# Project-PCB.net
KiCad netlist of a schematic drawn in Altium Designer
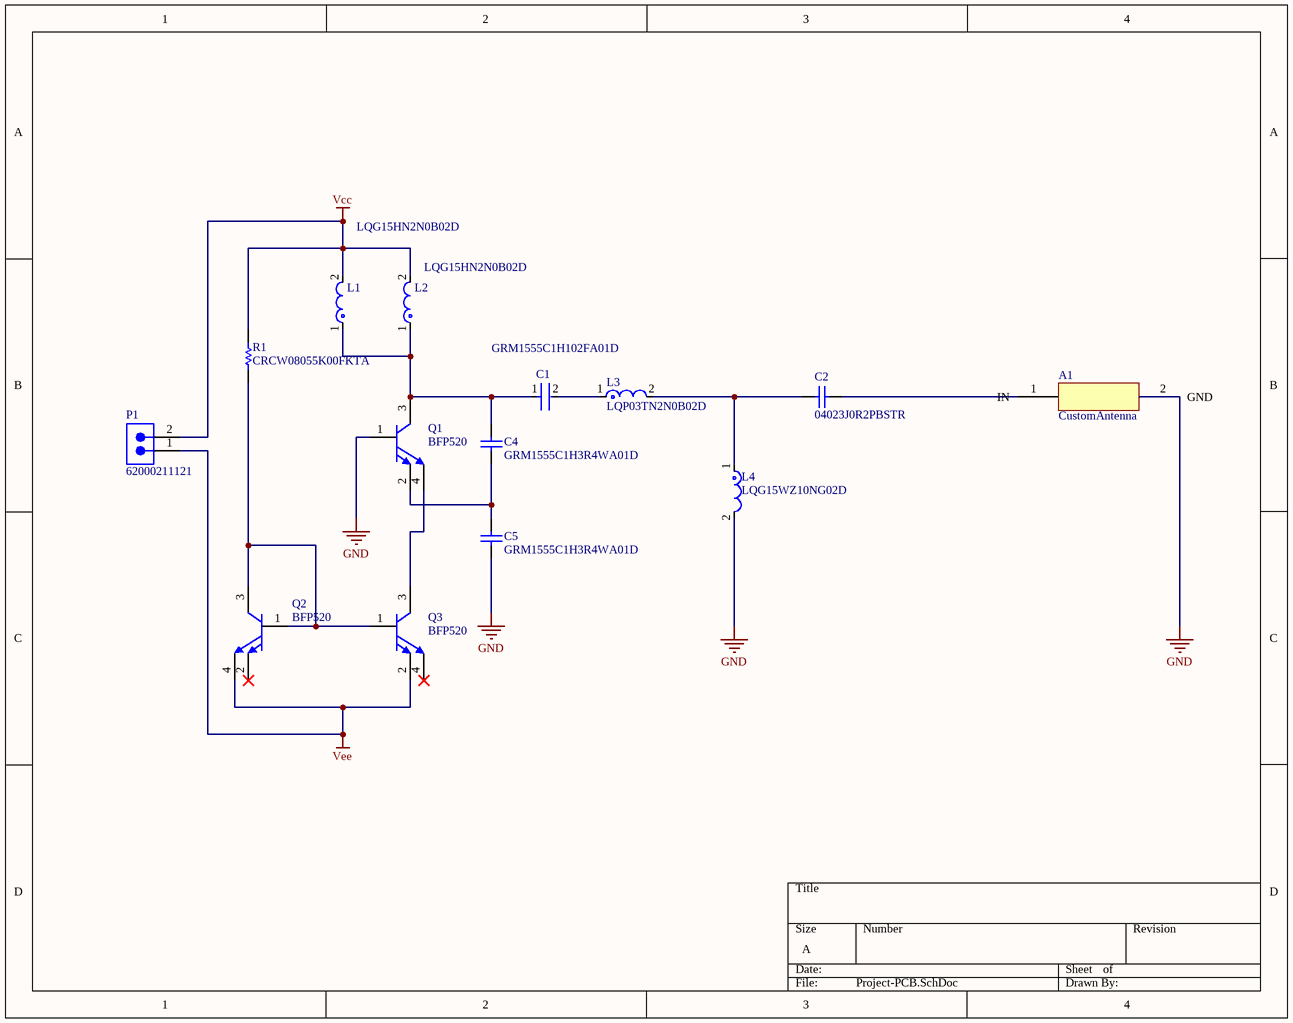
[diagram p0: Project-PCB.SchDoc]

(export (version "E")
  (design (tool "Eeschema 10.0.6"))
  (components
    (comp (ref "A1")
      (value "CustomAntenna")
      (footprint "CustomAntennaFootprint")
      (description "Custom Antenna from CST")
      (libsource (lib "AntennaLib") (part "CustomAntenna"))
    )
    (comp (ref "C1")
      (value "GRM1555C1H102FA01D")
      (footprint "FP-GRM155-0_05-IPC_B")
      (description "Chip Multilayer Ceramic Capacitors for General Purpose, 0402, 1000pF, C0G, 30ppm/°C, 1%, 50V")
      (fields (field (name "TOLERANCE") "1%") (field (name "VOLTAGE") "50V"))
      (libsource (lib "Altium Content Vault") (part "02cd4be3c70576c341d710602a673aa"))
    )
    (comp (ref "C2")
      (value "04023J0R2PBSTR")
      (footprint "CAPC1006X50X20LL10T10")
      (fields (field (name "MANUFACTURER") "AVX Interconnect / Elco"))
      (libsource (lib "Altium Content Vault") (part "CAP"))
    )
    (comp (ref "C4")
      (value "GRM1555C1H3R4WA01D")
      (footprint "CAPC1005X55X25ML05T10")
      (fields (field (name "MANUFACTURER") "Murata"))
      (libsource (lib "Altium Content Vault") (part "CAP"))
    )
    (comp (ref "C5")
      (value "GRM1555C1H3R4WA01D")
      (footprint "CAPC1005X55X25ML05T10")
      (fields (field (name "MANUFACTURER") "Murata"))
      (libsource (lib "Altium Content Vault") (part "CAP"))
    )
    (comp (ref "L1")
      (value "LQG15HN2N0B02D")
      (footprint "FP-LQG15HH_02-MFG")
      (description "Multilayer type RF Inductor 2nH ±0.1nH 0.09Ω 900mA 0402")
      (libsource (lib "Altium Content Vault") (part "4cc4b267dca4c8e51f7102f422741d8"))
    )
    (comp (ref "L2")
      (value "LQG15HN2N0B02D")
      (footprint "FP-LQG15HH_02-MFG")
      (description "Multilayer type RF Inductor 2nH ±0.1nH 0.09Ω 900mA 0402")
      (libsource (lib "Altium Content Vault") (part "4cc4b267dca4c8e51f7102f422741d8"))
    )
    (comp (ref "L3")
      (value "LQP03TN2N0B02D")
      (footprint "FP-LQP03TG_02-IPC_A")
      (description "Film type RF Inductor 2nH ±0.1nH 600mA 0.15Ω 0201 (0603)")
      (libsource (lib "Altium Content Vault") (part "4cc4b267dca4c8e51f7102f422741d8"))
    )
    (comp (ref "L4")
      (value "LQG15WZ10NG02D")
      (footprint "FP-LQG15WH_02-IPC_A")
      (description "Multilayer type Inductor for Automotive 10nH ±2% 0.19Ω 500mA 0402")
      (libsource (lib "Altium Content Vault") (part "4cc4b267dca4c8e51f7102f422741d8"))
    )
    (comp (ref "P1")
      (value "62000211121")
      (footprint "62000211121")
      (libsource (lib "Altium Content Vault") (part "Header_Male_1R_02P"))
    )
    (comp (ref "Q1")
      (value "BFP520")
      (footprint "INF-SOT343_V")
      (description "NPN Silicon RF Transistor, 2.5 V VCEO, 40 mA IC, 23.5 dB Gmax, SOT343, Green")
      (fields (field (name "MANUFACTURER") "Infineon"))
      (libsource (lib "Altium Content Vault") (part "INF-BFP520-4"))
    )
    (comp (ref "Q2")
      (value "BFP520")
      (footprint "INF-SOT343_V")
      (description "NPN Silicon RF Transistor, 2.5 V VCEO, 40 mA IC, 23.5 dB Gmax, SOT343, Green")
      (fields (field (name "MANUFACTURER") "Infineon"))
      (libsource (lib "Altium Content Vault") (part "INF-BFP520-4"))
    )
    (comp (ref "Q3")
      (value "BFP520")
      (footprint "INF-SOT343_V")
      (description "NPN Silicon RF Transistor, 2.5 V VCEO, 40 mA IC, 23.5 dB Gmax, SOT343, Green")
      (fields (field (name "MANUFACTURER") "Infineon"))
      (libsource (lib "Altium Content Vault") (part "INF-BFP520-4"))
    )
    (comp (ref "R1")
      (value "CRCW08055K00FKTA")
      (footprint "RESC2013X50X30ML20T20")
      (fields (field (name "MANUFACTURER") "Vishay Dale"))
      (libsource (lib "Altium Content Vault") (part "RES"))
    )
  )
  (nets
    (net (code "1") (name "GND") (class "Default")
      (node (ref "A1") (pin "2") (pinfunction "GND_2") (pintype "passive"))
      (node (ref "C5") (pin "1") (pinfunction "1_1") (pintype "passive"))
      (node (ref "L4") (pin "2") (pinfunction "2_2") (pintype "passive"))
      (node (ref "Q1") (pin "1") (pinfunction "B_1") (pintype "passive"))
    )
    (net (code "2") (name "Net-(A1-IN)") (class "Default")
      (node (ref "A1") (pin "1") (pinfunction "IN_1") (pintype "passive"))
      (node (ref "C2") (pin "2") (pinfunction "2_2") (pintype "passive"))
    )
    (net (code "3") (name "Net-(C1-Pad2)") (class "Default")
      (node (ref "C1") (pin "2") (pinfunction "2_2") (pintype "passive"))
      (node (ref "L3") (pin "1") (pinfunction "1_1") (pintype "passive"))
    )
    (net (code "4") (name "Net-(C2-Pad1)") (class "Default")
      (node (ref "C2") (pin "1") (pinfunction "1_1") (pintype "passive"))
      (node (ref "L3") (pin "2") (pinfunction "2_2") (pintype "passive"))
      (node (ref "L4") (pin "1") (pinfunction "1_1") (pintype "passive"))
    )
    (net (code "5") (name "Net-(C4-Pad1)") (class "Default")
      (node (ref "C4") (pin "1") (pinfunction "1_1") (pintype "passive"))
      (node (ref "C5") (pin "2") (pinfunction "2_2") (pintype "passive"))
      (node (ref "Q1") (pin "2") (pinfunction "E_2") (pintype "passive"))
    )
    (net (code "6") (name "Net-(Q1-C)") (class "Default")
      (node (ref "C1") (pin "1") (pinfunction "1_1") (pintype "passive"))
      (node (ref "C4") (pin "2") (pinfunction "2_2") (pintype "passive"))
      (node (ref "L1") (pin "1") (pinfunction "1_1") (pintype "passive"))
      (node (ref "L2") (pin "1") (pinfunction "1_1") (pintype "passive"))
      (node (ref "Q1") (pin "3") (pinfunction "C_3") (pintype "passive"))
    )
    (net (code "7") (name "Net-(Q2-B)") (class "Default")
      (node (ref "Q2") (pin "1") (pinfunction "B_1") (pintype "passive"))
      (node (ref "Q2") (pin "3") (pinfunction "C_3") (pintype "passive"))
      (node (ref "Q3") (pin "1") (pinfunction "B_1") (pintype "passive"))
      (node (ref "R1") (pin "1") (pinfunction "1_1") (pintype "passive"))
    )
    (net (code "8") (name "Net-(Q3-C)") (class "Default")
      (node (ref "Q1") (pin "4") (pinfunction "E_4") (pintype "passive"))
      (node (ref "Q3") (pin "3") (pinfunction "C_3") (pintype "passive"))
    )
    (net (code "9") (name "Vcc") (class "Default")
      (node (ref "L1") (pin "2") (pinfunction "2_2") (pintype "passive"))
      (node (ref "L2") (pin "2") (pinfunction "2_2") (pintype "passive"))
      (node (ref "P1") (pin "2") (pinfunction "2_2") (pintype "passive"))
      (node (ref "R1") (pin "2") (pinfunction "2_2") (pintype "passive"))
    )
    (net (code "10") (name "Vee") (class "Default")
      (node (ref "P1") (pin "1") (pinfunction "1_1") (pintype "passive"))
      (node (ref "Q2") (pin "4") (pinfunction "E_4") (pintype "passive"))
      (node (ref "Q3") (pin "2") (pinfunction "E_2") (pintype "passive"))
    )
    (net (code "11") (name "unconnected-(Q2-E-Pad2)") (class "Default")
      (node (ref "Q2") (pin "2") (pinfunction "E_2") (pintype "passive+no_connect"))
    )
    (net (code "12") (name "unconnected-(Q3-E-Pad4)") (class "Default")
      (node (ref "Q3") (pin "4") (pinfunction "E_4") (pintype "passive+no_connect"))
    )
  )
)
